# ports.net
KiCad netlist of a schematic drawn in Altium Designer
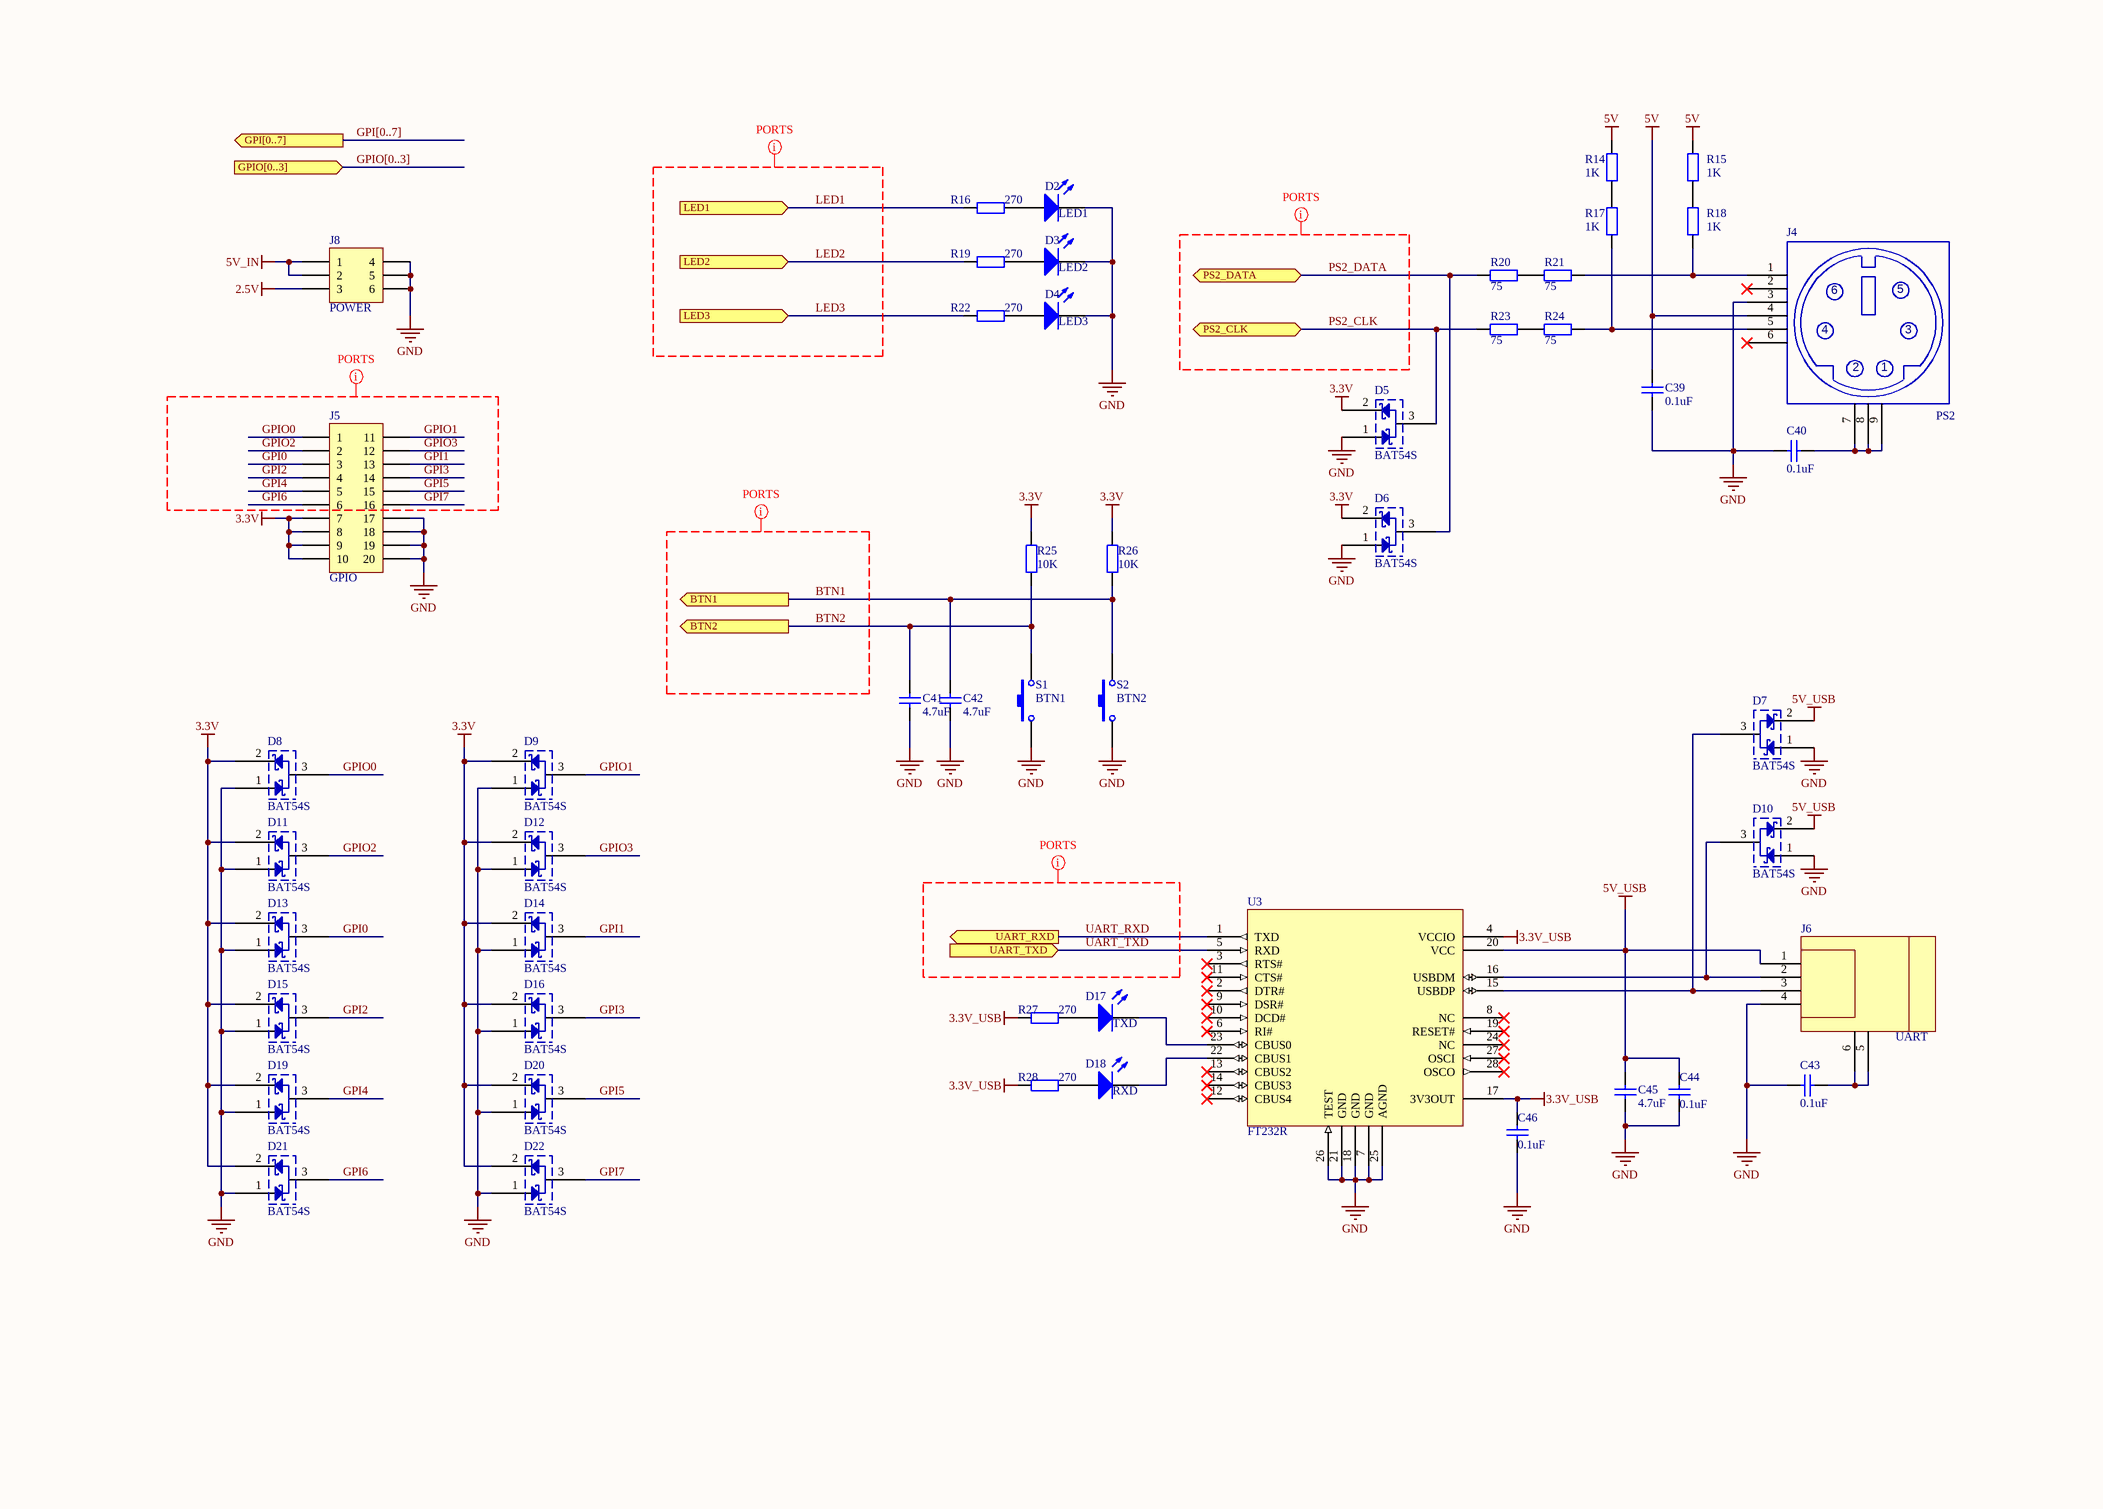
[diagram p0: ports.SchDoc]

(export (version "E")
  (design (tool "Eeschema 10.0.6"))
  (components
    (comp (ref "C39")
      (value "0.1uF")
      (footprint "0402")
      (description "Capacitor")
      (fields (field (name "Comment") "Cap") (field (name "PUBLISHER") "Altium Limited"))
      (libsource (lib "Miscellaneous Devices") (part "Cap"))
    )
    (comp (ref "C40")
      (value "0.1uF")
      (footprint "0402")
      (description "Capacitor")
      (fields (field (name "Comment") "Cap") (field (name "PUBLISHER") "Altium Limited"))
      (libsource (lib "Miscellaneous Devices") (part "Cap"))
    )
    (comp (ref "C41")
      (value "4.7uF")
      (footprint "C0805")
      (description "Capacitor")
      (fields (field (name "Comment") "Cap") (field (name "PUBLISHER") "Altium Limited"))
      (libsource (lib "Miscellaneous Devices") (part "Cap"))
    )
    (comp (ref "C42")
      (value "4.7uF")
      (footprint "C0805")
      (description "Capacitor")
      (fields (field (name "Comment") "Cap") (field (name "PUBLISHER") "Altium Limited"))
      (libsource (lib "Miscellaneous Devices") (part "Cap"))
    )
    (comp (ref "C43")
      (value "0.1uF")
      (footprint "0402")
      (description "Capacitor")
      (fields (field (name "Comment") "Cap") (field (name "PUBLISHER") "Altium Limited"))
      (libsource (lib "Miscellaneous Devices") (part "Cap"))
    )
    (comp (ref "C44")
      (value "0.1uF")
      (footprint "0402")
      (description "Capacitor")
      (fields (field (name "Comment") "Cap") (field (name "PUBLISHER") "Altium Limited"))
      (libsource (lib "Miscellaneous Devices") (part "Cap"))
    )
    (comp (ref "C45")
      (value "4.7uF")
      (footprint "C0805")
      (description "Capacitor")
      (fields (field (name "Comment") "Cap") (field (name "PUBLISHER") "Altium Limited"))
      (libsource (lib "Miscellaneous Devices") (part "Cap"))
    )
    (comp (ref "C46")
      (value "0.1uF")
      (footprint "0402")
      (description "Capacitor")
      (fields (field (name "Comment") "Cap") (field (name "PUBLISHER") "Altium Limited"))
      (libsource (lib "Miscellaneous Devices") (part "Cap"))
    )
    (comp (ref "D2")
      (value "LED1")
      (footprint "LED")
      (description "Amber")
      (fields (field (name "PUBLISHER") "Altium Limited"))
      (libsource (lib "Miscellaneous Devices") (part "LED3"))
    )
    (comp (ref "D3")
      (value "LED2")
      (footprint "LED")
      (description "Amber")
      (fields (field (name "PUBLISHER") "Altium Limited"))
      (libsource (lib "Miscellaneous Devices") (part "LED3"))
    )
    (comp (ref "D4")
      (value "LED3")
      (footprint "LED")
      (description "Amber")
      (fields (field (name "PUBLISHER") "Altium Limited"))
      (libsource (lib "Miscellaneous Devices") (part "LED3"))
    )
    (comp (ref "D5")
      (value "BAT54S")
      (footprint "SOT23_BAT54S")
      (libsource (lib "FPGA_board") (part "BAT54S"))
    )
    (comp (ref "D6")
      (value "BAT54S")
      (footprint "SOT23_BAT54S")
      (libsource (lib "FPGA_board") (part "BAT54S"))
    )
    (comp (ref "D7")
      (value "BAT54S")
      (footprint "SOT23_BAT54S")
      (libsource (lib "FPGA_board") (part "BAT54S"))
    )
    (comp (ref "D8")
      (value "BAT54S")
      (footprint "SOT23_BAT54S")
      (libsource (lib "FPGA_board") (part "BAT54S"))
    )
    (comp (ref "D9")
      (value "BAT54S")
      (footprint "SOT23_BAT54S")
      (libsource (lib "FPGA_board") (part "BAT54S"))
    )
    (comp (ref "D10")
      (value "BAT54S")
      (footprint "SOT23_BAT54S")
      (libsource (lib "FPGA_board") (part "BAT54S"))
    )
    (comp (ref "D11")
      (value "BAT54S")
      (footprint "SOT23_BAT54S")
      (libsource (lib "FPGA_board") (part "BAT54S"))
    )
    (comp (ref "D12")
      (value "BAT54S")
      (footprint "SOT23_BAT54S")
      (libsource (lib "FPGA_board") (part "BAT54S"))
    )
    (comp (ref "D13")
      (value "BAT54S")
      (footprint "SOT23_BAT54S")
      (libsource (lib "FPGA_board") (part "BAT54S"))
    )
    (comp (ref "D14")
      (value "BAT54S")
      (footprint "SOT23_BAT54S")
      (libsource (lib "FPGA_board") (part "BAT54S"))
    )
    (comp (ref "D15")
      (value "BAT54S")
      (footprint "SOT23_BAT54S")
      (libsource (lib "FPGA_board") (part "BAT54S"))
    )
    (comp (ref "D16")
      (value "BAT54S")
      (footprint "SOT23_BAT54S")
      (libsource (lib "FPGA_board") (part "BAT54S"))
    )
    (comp (ref "D17")
      (value "TXD")
      (footprint "LED")
      (description "Green")
      (fields (field (name "PUBLISHER") "Altium Limited"))
      (libsource (lib "Miscellaneous Devices") (part "LED3"))
    )
    (comp (ref "D18")
      (value "RXD")
      (footprint "LED")
      (description "Red")
      (fields (field (name "PUBLISHER") "Altium Limited"))
      (libsource (lib "Miscellaneous Devices") (part "LED3"))
    )
    (comp (ref "D19")
      (value "BAT54S")
      (footprint "SOT23_BAT54S")
      (libsource (lib "FPGA_board") (part "BAT54S"))
    )
    (comp (ref "D20")
      (value "BAT54S")
      (footprint "SOT23_BAT54S")
      (libsource (lib "FPGA_board") (part "BAT54S"))
    )
    (comp (ref "D21")
      (value "BAT54S")
      (footprint "SOT23_BAT54S")
      (libsource (lib "FPGA_board") (part "BAT54S"))
    )
    (comp (ref "D22")
      (value "BAT54S")
      (footprint "SOT23_BAT54S")
      (libsource (lib "FPGA_board") (part "BAT54S"))
    )
    (comp (ref "J4") (value "PS2") (footprint "PS2-6PIN") (libsource (lib "FPGA_board") (part "PS2_Socket")))
    (comp (ref "J5")
      (value "GPIO")
      (footprint "HDR2X10_CEN")
      (description "Header, 10-Pin, Dual row")
      (fields (field (name "PUBLISHER") "Altium Limited"))
      (libsource (lib "Miscellaneous Connectors") (part "Header 10X2A"))
    )
    (comp (ref "J6") (value "UART") (footprint "USB_B") (libsource (lib "FPGA_board") (part "USB_B")))
    (comp (ref "J8")
      (value "POWER")
      (footprint "HDR2X3_CEN")
      (description "Header, 3-Pin, Dual row")
      (fields (field (name "PUBLISHER") "Altium Limited"))
      (libsource (lib "Miscellaneous Connectors") (part "Header 3X2A"))
    )
    (comp (ref "R14")
      (value "1K")
      (footprint "J1-0603")
      (description "Resistor")
      (fields (field (name "Comment") "Res2") (field (name "PUBLISHER") "Altium Limited"))
      (libsource (lib "") (part "Res2_1"))
    )
    (comp (ref "R15")
      (value "1K")
      (footprint "J1-0603")
      (description "Resistor")
      (fields (field (name "Comment") "Res2") (field (name "PUBLISHER") "Altium Limited"))
      (libsource (lib "") (part "Res2_1"))
    )
    (comp (ref "R16")
      (value "270")
      (footprint "6-0805_N")
      (description "Resistor")
      (fields (field (name "Comment") "Res2") (field (name "PUBLISHER") "Altium Limited"))
      (libsource (lib "Miscellaneous Devices") (part "Res2"))
    )
    (comp (ref "R17")
      (value "1K")
      (footprint "J1-0603")
      (description "Resistor")
      (fields (field (name "Comment") "Res2") (field (name "PUBLISHER") "Altium Limited"))
      (libsource (lib "") (part "Res2_1"))
    )
    (comp (ref "R18")
      (value "1K")
      (footprint "J1-0603")
      (description "Resistor")
      (fields (field (name "Comment") "Res2") (field (name "PUBLISHER") "Altium Limited"))
      (libsource (lib "") (part "Res2_1"))
    )
    (comp (ref "R19")
      (value "270")
      (footprint "6-0805_N")
      (description "Resistor")
      (fields (field (name "Comment") "Res2") (field (name "PUBLISHER") "Altium Limited"))
      (libsource (lib "Miscellaneous Devices") (part "Res2"))
    )
    (comp (ref "R20")
      (value "75")
      (footprint "J1-0603")
      (description "Resistor")
      (fields (field (name "Comment") "Res2") (field (name "PUBLISHER") "Altium Limited"))
      (libsource (lib "") (part "Res2_3"))
    )
    (comp (ref "R21")
      (value "75")
      (footprint "J1-0603")
      (description "Resistor")
      (fields (field (name "Comment") "Res2") (field (name "PUBLISHER") "Altium Limited"))
      (libsource (lib "") (part "Res2_3"))
    )
    (comp (ref "R22")
      (value "270")
      (footprint "6-0805_N")
      (description "Resistor")
      (fields (field (name "Comment") "Res2") (field (name "PUBLISHER") "Altium Limited"))
      (libsource (lib "Miscellaneous Devices") (part "Res2"))
    )
    (comp (ref "R23")
      (value "75")
      (footprint "J1-0603")
      (description "Resistor")
      (fields (field (name "Comment") "Res2") (field (name "PUBLISHER") "Altium Limited"))
      (libsource (lib "") (part "Res2_3"))
    )
    (comp (ref "R24")
      (value "75")
      (footprint "J1-0603")
      (description "Resistor")
      (fields (field (name "Comment") "Res2") (field (name "PUBLISHER") "Altium Limited"))
      (libsource (lib "") (part "Res2_3"))
    )
    (comp (ref "R25")
      (value "10K")
      (footprint "J1-0603")
      (description "Resistor")
      (fields (field (name "Comment") "Res2") (field (name "PUBLISHER") "Altium Limited"))
      (libsource (lib "") (part "Res2_2"))
    )
    (comp (ref "R26")
      (value "10K")
      (footprint "J1-0603")
      (description "Resistor")
      (fields (field (name "Comment") "Res2") (field (name "PUBLISHER") "Altium Limited"))
      (libsource (lib "") (part "Res2_2"))
    )
    (comp (ref "R27")
      (value "270")
      (footprint "6-0805_N")
      (description "Resistor")
      (fields (field (name "Comment") "Res2") (field (name "PUBLISHER") "Altium Limited"))
      (libsource (lib "Miscellaneous Devices") (part "Res2"))
    )
    (comp (ref "R28")
      (value "270")
      (footprint "6-0805_N")
      (description "Resistor")
      (fields (field (name "Comment") "Res2") (field (name "PUBLISHER") "Altium Limited"))
      (libsource (lib "Miscellaneous Devices") (part "Res2"))
    )
    (comp (ref "S1")
      (value "BTN1")
      (footprint "PUSHBUTTON")
      (description "Switch")
      (fields (field (name "PUBLISHER") "Altium Limited"))
      (libsource (lib "Miscellaneous Devices") (part "SW-PB"))
    )
    (comp (ref "S2")
      (value "BTN2")
      (footprint "PUSHBUTTON")
      (description "Switch")
      (fields (field (name "PUBLISHER") "Altium Limited"))
      (libsource (lib "Miscellaneous Devices") (part "SW-PB"))
    )
    (comp (ref "U3") (value "FT232R") (footprint "SSOP28") (libsource (lib "FPGA_board") (part "FT232R")))
  )
  (nets
    (net (code "1") (name "/BTN1") (class "Default")
      (node (ref "C42") (pin "2") (pinfunction "2_2") (pintype "passive"))
      (node (ref "R26") (pin "2") (pinfunction "2_2") (pintype "passive"))
      (node (ref "S2") (pin "2") (pinfunction "2_2") (pintype "passive"))
    )
    (net (code "2") (name "/BTN2") (class "Default")
      (node (ref "C41") (pin "2") (pinfunction "2_2") (pintype "passive"))
      (node (ref "R25") (pin "2") (pinfunction "2_2") (pintype "passive"))
      (node (ref "S1") (pin "2") (pinfunction "2_2") (pintype "passive"))
    )
    (net (code "3") (name "/GPI0") (class "Default")
      (node (ref "D13") (pin "3") (pinfunction "3_3") (pintype "passive"))
      (node (ref "J5") (pin "3") (pinfunction "3_3") (pintype "passive"))
    )
    (net (code "4") (name "/GPI1") (class "Default")
      (node (ref "D14") (pin "3") (pinfunction "3_3") (pintype "passive"))
      (node (ref "J5") (pin "13") (pinfunction "13_13") (pintype "passive"))
    )
    (net (code "5") (name "/GPI2") (class "Default")
      (node (ref "D15") (pin "3") (pinfunction "3_3") (pintype "passive"))
      (node (ref "J5") (pin "4") (pinfunction "4_4") (pintype "passive"))
    )
    (net (code "6") (name "/GPI3") (class "Default")
      (node (ref "D16") (pin "3") (pinfunction "3_3") (pintype "passive"))
      (node (ref "J5") (pin "14") (pinfunction "14_14") (pintype "passive"))
    )
    (net (code "7") (name "/GPI4") (class "Default")
      (node (ref "D19") (pin "3") (pinfunction "3_3") (pintype "passive"))
      (node (ref "J5") (pin "5") (pinfunction "5_5") (pintype "passive"))
    )
    (net (code "8") (name "/GPI5") (class "Default")
      (node (ref "D20") (pin "3") (pinfunction "3_3") (pintype "passive"))
      (node (ref "J5") (pin "15") (pinfunction "15_15") (pintype "passive"))
    )
    (net (code "9") (name "/GPI6") (class "Default")
      (node (ref "D21") (pin "3") (pinfunction "3_3") (pintype "passive"))
      (node (ref "J5") (pin "6") (pinfunction "6_6") (pintype "passive"))
    )
    (net (code "10") (name "/GPI7") (class "Default")
      (node (ref "D22") (pin "3") (pinfunction "3_3") (pintype "passive"))
      (node (ref "J5") (pin "16") (pinfunction "16_16") (pintype "passive"))
    )
    (net (code "11") (name "/GPIO0") (class "Default")
      (node (ref "D8") (pin "3") (pinfunction "3_3") (pintype "passive"))
      (node (ref "J5") (pin "1") (pinfunction "1_1") (pintype "passive"))
    )
    (net (code "12") (name "/GPIO1") (class "Default")
      (node (ref "D9") (pin "3") (pinfunction "3_3") (pintype "passive"))
      (node (ref "J5") (pin "11") (pinfunction "11_11") (pintype "passive"))
    )
    (net (code "13") (name "/GPIO2") (class "Default")
      (node (ref "D11") (pin "3") (pinfunction "3_3") (pintype "passive"))
      (node (ref "J5") (pin "2") (pinfunction "2_2") (pintype "passive"))
    )
    (net (code "14") (name "/GPIO3") (class "Default")
      (node (ref "D12") (pin "3") (pinfunction "3_3") (pintype "passive"))
      (node (ref "J5") (pin "12") (pinfunction "12_12") (pintype "passive"))
    )
    (net (code "17") (name "/LED1") (class "Default")
      (node (ref "R16") (pin "2") (pinfunction "2_2") (pintype "passive"))
    )
    (net (code "18") (name "/LED2") (class "Default")
      (node (ref "R19") (pin "2") (pinfunction "2_2") (pintype "passive"))
    )
    (net (code "19") (name "/LED3") (class "Default")
      (node (ref "R22") (pin "2") (pinfunction "2_2") (pintype "passive"))
    )
    (net (code "20") (name "/PS2_CLK") (class "Default")
      (node (ref "D5") (pin "3") (pinfunction "3_3") (pintype "passive"))
      (node (ref "R23") (pin "1") (pinfunction "1_1") (pintype "passive"))
    )
    (net (code "21") (name "/PS2_DATA") (class "Default")
      (node (ref "D6") (pin "3") (pinfunction "3_3") (pintype "passive"))
      (node (ref "R20") (pin "1") (pinfunction "1_1") (pintype "passive"))
    )
    (net (code "22") (name "/UART_RXD") (class "Default")
      (node (ref "U3") (pin "1") (pinfunction "TXD_1") (pintype "output"))
    )
    (net (code "23") (name "/UART_TXD") (class "Default")
      (node (ref "U3") (pin "5") (pinfunction "RXD_5") (pintype "input"))
    )
    (net (code "24") (name "2.5V") (class "Default")
      (node (ref "J8") (pin "3") (pinfunction "3_3") (pintype "passive"))
    )
    (net (code "25") (name "3.3V") (class "Default")
      (node (ref "D11") (pin "2") (pinfunction "2_2") (pintype "passive"))
      (node (ref "D12") (pin "2") (pinfunction "2_2") (pintype "passive"))
      (node (ref "D13") (pin "2") (pinfunction "2_2") (pintype "passive"))
      (node (ref "D14") (pin "2") (pinfunction "2_2") (pintype "passive"))
      (node (ref "D15") (pin "2") (pinfunction "2_2") (pintype "passive"))
      (node (ref "D16") (pin "2") (pinfunction "2_2") (pintype "passive"))
      (node (ref "D19") (pin "2") (pinfunction "2_2") (pintype "passive"))
      (node (ref "D20") (pin "2") (pinfunction "2_2") (pintype "passive"))
      (node (ref "D21") (pin "2") (pinfunction "2_2") (pintype "passive"))
      (node (ref "D22") (pin "2") (pinfunction "2_2") (pintype "passive"))
      (node (ref "D5") (pin "2") (pinfunction "2_2") (pintype "passive"))
      (node (ref "D6") (pin "2") (pinfunction "2_2") (pintype "passive"))
      (node (ref "D8") (pin "2") (pinfunction "2_2") (pintype "passive"))
      (node (ref "D9") (pin "2") (pinfunction "2_2") (pintype "passive"))
      (node (ref "J5") (pin "10") (pinfunction "10_10") (pintype "passive"))
      (node (ref "J5") (pin "7") (pinfunction "7_7") (pintype "passive"))
      (node (ref "J5") (pin "8") (pinfunction "8_8") (pintype "passive"))
      (node (ref "J5") (pin "9") (pinfunction "9_9") (pintype "passive"))
      (node (ref "R25") (pin "1") (pinfunction "1_1") (pintype "passive"))
      (node (ref "R26") (pin "1") (pinfunction "1_1") (pintype "passive"))
    )
    (net (code "26") (name "3.3V_USB") (class "Default")
      (node (ref "C46") (pin "1") (pinfunction "1_1") (pintype "passive"))
      (node (ref "R27") (pin "2") (pinfunction "2_2") (pintype "passive"))
      (node (ref "R28") (pin "2") (pinfunction "2_2") (pintype "passive"))
      (node (ref "U3") (pin "17") (pinfunction "3V3OUT_17") (pintype "power_in"))
      (node (ref "U3") (pin "4") (pinfunction "VCCIO_4") (pintype "power_in"))
    )
    (net (code "27") (name "5V") (class "Default")
      (node (ref "C39") (pin "2") (pinfunction "2_2") (pintype "passive"))
      (node (ref "J4") (pin "4") (pintype "passive"))
      (node (ref "R14") (pin "2") (pinfunction "2_2") (pintype "passive"))
      (node (ref "R15") (pin "2") (pinfunction "2_2") (pintype "passive"))
    )
    (net (code "28") (name "5V_IN") (class "Default")
      (node (ref "J8") (pin "1") (pinfunction "1_1") (pintype "passive"))
      (node (ref "J8") (pin "2") (pinfunction "2_2") (pintype "passive"))
    )
    (net (code "29") (name "5V_USB") (class "Default")
      (node (ref "C44") (pin "1") (pinfunction "1_1") (pintype "passive"))
      (node (ref "C45") (pin "2") (pinfunction "2_2") (pintype "passive"))
      (node (ref "D10") (pin "2") (pinfunction "2_2") (pintype "passive"))
      (node (ref "D7") (pin "2") (pinfunction "2_2") (pintype "passive"))
      (node (ref "J6") (pin "1") (pintype "passive"))
      (node (ref "U3") (pin "20") (pinfunction "VCC_20") (pintype "power_in"))
    )
    (net (code "30") (name "GND") (class "Default")
      (node (ref "C39") (pin "1") (pinfunction "1_1") (pintype "passive"))
      (node (ref "C40") (pin "1") (pinfunction "1_1") (pintype "passive"))
      (node (ref "C41") (pin "1") (pinfunction "1_1") (pintype "passive"))
      (node (ref "C42") (pin "1") (pinfunction "1_1") (pintype "passive"))
      (node (ref "C43") (pin "1") (pinfunction "1_1") (pintype "passive"))
      (node (ref "C44") (pin "2") (pinfunction "2_2") (pintype "passive"))
      (node (ref "C45") (pin "1") (pinfunction "1_1") (pintype "passive"))
      (node (ref "C46") (pin "2") (pinfunction "2_2") (pintype "passive"))
      (node (ref "D10") (pin "1") (pinfunction "1_1") (pintype "passive"))
      (node (ref "D11") (pin "1") (pinfunction "1_1") (pintype "passive"))
      (node (ref "D12") (pin "1") (pinfunction "1_1") (pintype "passive"))
      (node (ref "D13") (pin "1") (pinfunction "1_1") (pintype "passive"))
      (node (ref "D14") (pin "1") (pinfunction "1_1") (pintype "passive"))
      (node (ref "D15") (pin "1") (pinfunction "1_1") (pintype "passive"))
      (node (ref "D16") (pin "1") (pinfunction "1_1") (pintype "passive"))
      (node (ref "D19") (pin "1") (pinfunction "1_1") (pintype "passive"))
      (node (ref "D2") (pin "2") (pinfunction "K_2") (pintype "passive"))
      (node (ref "D20") (pin "1") (pinfunction "1_1") (pintype "passive"))
      (node (ref "D21") (pin "1") (pinfunction "1_1") (pintype "passive"))
      (node (ref "D22") (pin "1") (pinfunction "1_1") (pintype "passive"))
      (node (ref "D3") (pin "2") (pinfunction "K_2") (pintype "passive"))
      (node (ref "D4") (pin "2") (pinfunction "K_2") (pintype "passive"))
      (node (ref "D5") (pin "1") (pinfunction "1_1") (pintype "passive"))
      (node (ref "D6") (pin "1") (pinfunction "1_1") (pintype "passive"))
      (node (ref "D7") (pin "1") (pinfunction "1_1") (pintype "passive"))
      (node (ref "D8") (pin "1") (pinfunction "1_1") (pintype "passive"))
      (node (ref "D9") (pin "1") (pinfunction "1_1") (pintype "passive"))
      (node (ref "J4") (pin "3") (pintype "passive"))
      (node (ref "J5") (pin "17") (pinfunction "17_17") (pintype "passive"))
      (node (ref "J5") (pin "18") (pinfunction "18_18") (pintype "passive"))
      (node (ref "J5") (pin "19") (pinfunction "19_19") (pintype "passive"))
      (node (ref "J5") (pin "20") (pinfunction "20_20") (pintype "passive"))
      (node (ref "J6") (pin "4") (pintype "passive"))
      (node (ref "J8") (pin "4") (pinfunction "4_4") (pintype "passive"))
      (node (ref "J8") (pin "5") (pinfunction "5_5") (pintype "passive"))
      (node (ref "J8") (pin "6") (pinfunction "6_6") (pintype "passive"))
      (node (ref "S1") (pin "1") (pinfunction "1_1") (pintype "passive"))
      (node (ref "S2") (pin "1") (pinfunction "1_1") (pintype "passive"))
      (node (ref "U3") (pin "18") (pinfunction "GND_18") (pintype "power_in"))
      (node (ref "U3") (pin "21") (pinfunction "GND_21") (pintype "power_in"))
      (node (ref "U3") (pin "25") (pinfunction "AGND_25") (pintype "power_in"))
      (node (ref "U3") (pin "26") (pinfunction "TEST_26") (pintype "input"))
      (node (ref "U3") (pin "7") (pinfunction "GND_7") (pintype "power_in"))
    )
    (net (code "31") (name "Net-(C40-Pad2)") (class "Default")
      (node (ref "C40") (pin "2") (pinfunction "2_2") (pintype "passive"))
      (node (ref "J4") (pin "7") (pintype "passive"))
      (node (ref "J4") (pin "8") (pintype "passive"))
      (node (ref "J4") (pin "9") (pintype "passive"))
    )
    (net (code "32") (name "Net-(C43-Pad2)") (class "Default")
      (node (ref "C43") (pin "2") (pinfunction "2_2") (pintype "passive"))
      (node (ref "J6") (pin "5") (pintype "passive"))
      (node (ref "J6") (pin "6") (pintype "passive"))
    )
    (net (code "33") (name "Net-(D2-A)") (class "Default")
      (node (ref "D2") (pin "1") (pinfunction "A_1") (pintype "passive"))
      (node (ref "R16") (pin "1") (pinfunction "1_1") (pintype "passive"))
    )
    (net (code "34") (name "Net-(D3-A)") (class "Default")
      (node (ref "D3") (pin "1") (pinfunction "A_1") (pintype "passive"))
      (node (ref "R19") (pin "1") (pinfunction "1_1") (pintype "passive"))
    )
    (net (code "35") (name "Net-(D4-A)") (class "Default")
      (node (ref "D4") (pin "1") (pinfunction "A_1") (pintype "passive"))
      (node (ref "R22") (pin "1") (pinfunction "1_1") (pintype "passive"))
    )
    (net (code "36") (name "Net-(D17-A)") (class "Default")
      (node (ref "D17") (pin "1") (pinfunction "A_1") (pintype "passive"))
      (node (ref "R27") (pin "1") (pinfunction "1_1") (pintype "passive"))
    )
    (net (code "37") (name "Net-(D17-K)") (class "Default")
      (node (ref "D17") (pin "2") (pinfunction "K_2") (pintype "passive"))
      (node (ref "U3") (pin "23") (pinfunction "CBUS0_23") (pintype "bidirectional"))
    )
    (net (code "38") (name "Net-(D18-A)") (class "Default")
      (node (ref "D18") (pin "1") (pinfunction "A_1") (pintype "passive"))
      (node (ref "R28") (pin "1") (pinfunction "1_1") (pintype "passive"))
    )
    (net (code "39") (name "Net-(D18-K)") (class "Default")
      (node (ref "D18") (pin "2") (pinfunction "K_2") (pintype "passive"))
      (node (ref "U3") (pin "22") (pinfunction "CBUS1_22") (pintype "bidirectional"))
    )
    (net (code "40") (name "Net-(J4-Pad1)") (class "Default")
      (node (ref "J4") (pin "1") (pintype "passive"))
      (node (ref "R18") (pin "1") (pinfunction "1_1") (pintype "passive"))
      (node (ref "R21") (pin "2") (pinfunction "2_2") (pintype "passive"))
    )
    (net (code "41") (name "Net-(J4-Pad5)") (class "Default")
      (node (ref "J4") (pin "5") (pintype "passive"))
      (node (ref "R17") (pin "1") (pinfunction "1_1") (pintype "passive"))
      (node (ref "R24") (pin "2") (pinfunction "2_2") (pintype "passive"))
    )
    (net (code "42") (name "Net-(R14-Pad1)") (class "Default")
      (node (ref "R14") (pin "1") (pinfunction "1_1") (pintype "passive"))
      (node (ref "R17") (pin "2") (pinfunction "2_2") (pintype "passive"))
    )
    (net (code "43") (name "Net-(R15-Pad1)") (class "Default")
      (node (ref "R15") (pin "1") (pinfunction "1_1") (pintype "passive"))
      (node (ref "R18") (pin "2") (pinfunction "2_2") (pintype "passive"))
    )
    (net (code "44") (name "Net-(R20-Pad2)") (class "Default")
      (node (ref "R20") (pin "2") (pinfunction "2_2") (pintype "passive"))
      (node (ref "R21") (pin "1") (pinfunction "1_1") (pintype "passive"))
    )
    (net (code "45") (name "Net-(R23-Pad2)") (class "Default")
      (node (ref "R23") (pin "2") (pinfunction "2_2") (pintype "passive"))
      (node (ref "R24") (pin "1") (pinfunction "1_1") (pintype "passive"))
    )
    (net (code "46") (name "Net-(U3-USBDM)") (class "Default")
      (node (ref "D10") (pin "3") (pinfunction "3_3") (pintype "passive"))
      (node (ref "J6") (pin "2") (pintype "passive"))
      (node (ref "U3") (pin "16") (pinfunction "USBDM_16") (pintype "bidirectional"))
    )
    (net (code "47") (name "Net-(U3-USBDP)") (class "Default")
      (node (ref "D7") (pin "3") (pinfunction "3_3") (pintype "passive"))
      (node (ref "J6") (pin "3") (pintype "passive"))
      (node (ref "U3") (pin "15") (pinfunction "USBDP_15") (pintype "bidirectional"))
    )
    (net (code "48") (name "unconnected-(J4-Pad2)") (class "Default")
      (node (ref "J4") (pin "2") (pintype "passive+no_connect"))
    )
    (net (code "49") (name "unconnected-(J4-Pad6)") (class "Default")
      (node (ref "J4") (pin "6") (pintype "passive+no_connect"))
    )
    (net (code "50") (name "unconnected-(U3-CBUS2-Pad13)") (class "Default")
      (node (ref "U3") (pin "13") (pinfunction "CBUS2_13") (pintype "bidirectional+no_connect"))
    )
    (net (code "51") (name "unconnected-(U3-CBUS3-Pad14)") (class "Default")
      (node (ref "U3") (pin "14") (pinfunction "CBUS3_14") (pintype "bidirectional+no_connect"))
    )
    (net (code "52") (name "unconnected-(U3-CBUS4-Pad12)") (class "Default")
      (node (ref "U3") (pin "12") (pinfunction "CBUS4_12") (pintype "bidirectional+no_connect"))
    )
    (net (code "53") (name "unconnected-(U3-CTS#-Pad11)") (class "Default")
      (node (ref "U3") (pin "11") (pinfunction "CTS#_11") (pintype "input+no_connect"))
    )
    (net (code "54") (name "unconnected-(U3-DCD#-Pad10)") (class "Default")
      (node (ref "U3") (pin "10") (pinfunction "DCD#_10") (pintype "input+no_connect"))
    )
    (net (code "55") (name "unconnected-(U3-DSR#-Pad9)") (class "Default")
      (node (ref "U3") (pin "9") (pinfunction "DSR#_9") (pintype "input+no_connect"))
    )
    (net (code "56") (name "unconnected-(U3-DTR#-Pad2)") (class "Default")
      (node (ref "U3") (pin "2") (pinfunction "DTR#_2") (pintype "output+no_connect"))
    )
    (net (code "57") (name "unconnected-(U3-NC-Pad8)") (class "Default")
      (node (ref "U3") (pin "8") (pinfunction "NC_8") (pintype "passive+no_connect"))
    )
    (net (code "58") (name "unconnected-(U3-NC-Pad24)") (class "Default")
      (node (ref "U3") (pin "24") (pinfunction "NC_24") (pintype "passive+no_connect"))
    )
    (net (code "59") (name "unconnected-(U3-OSCI-Pad27)") (class "Default")
      (node (ref "U3") (pin "27") (pinfunction "OSCI_27") (pintype "input+no_connect"))
    )
    (net (code "60") (name "unconnected-(U3-OSCO-Pad28)") (class "Default")
      (node (ref "U3") (pin "28") (pinfunction "OSCO_28") (pintype "output+no_connect"))
    )
    (net (code "61") (name "unconnected-(U3-RESET#-Pad19)") (class "Default")
      (node (ref "U3") (pin "19") (pinfunction "RESET#_19") (pintype "input+no_connect"))
    )
    (net (code "62") (name "unconnected-(U3-RI#-Pad6)") (class "Default")
      (node (ref "U3") (pin "6") (pinfunction "RI#_6") (pintype "input+no_connect"))
    )
    (net (code "63") (name "unconnected-(U3-RTS#-Pad3)") (class "Default")
      (node (ref "U3") (pin "3") (pinfunction "RTS#_3") (pintype "output+no_connect"))
    )
  )
)
